# ESP32_ublox_IMU_2020-12-27_17-32-34.net
KiCad netlist of a schematic drawn in Altium Designer
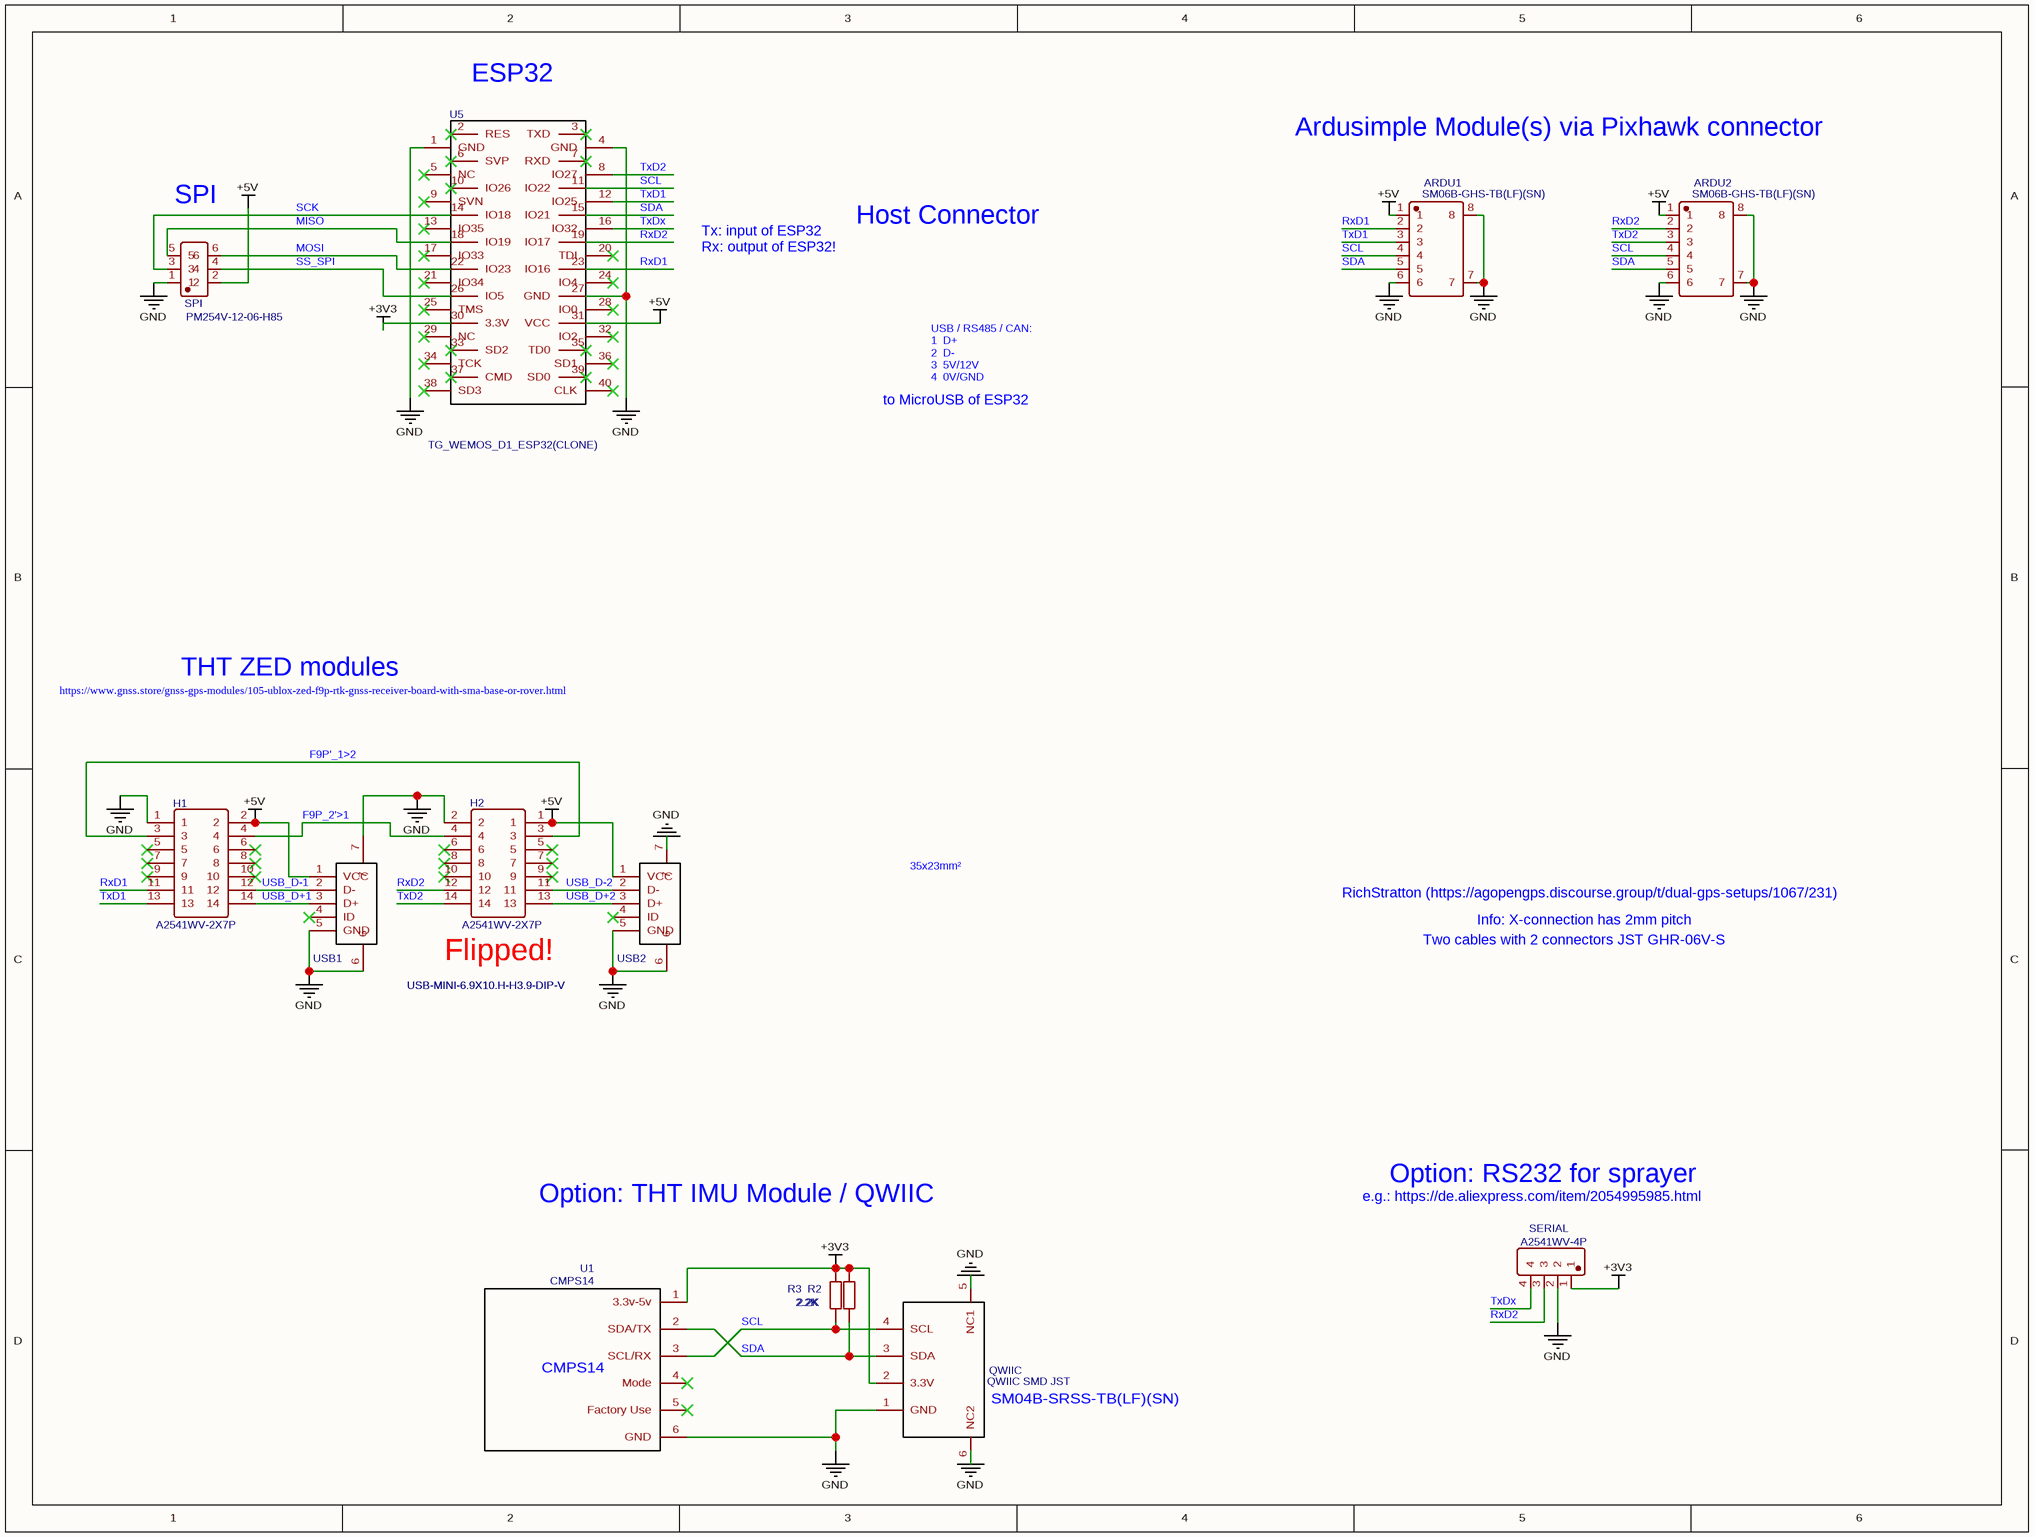
[diagram p0: ESP32 ublox IMU_2020-12-27_17-32-34.schdoc]

(export (version "E")
  (design (tool "Eeschema 10.0.6"))
  (components
    (comp (ref "ARDU1")
      (value "SM06B-GHS-TB(LF)(SN)")
      (fields (field (name "BOM_SUPPLIER PART") "C133065") (field (name "CONTRIBUTOR") "LCSC"))
      (libsource (lib "altium-import") (part "root_0_SM06B-GHS-TB(LF)(SN)_"))
    )
    (comp (ref "ARDU2")
      (value "SM06B-GHS-TB(LF)(SN)")
      (fields (field (name "BOM_SUPPLIER PART") "C133065") (field (name "CONTRIBUTOR") "LCSC"))
      (libsource (lib "altium-import") (part "root_0_SM06B-GHS-TB(LF)(SN)_"))
    )
    (comp (ref "H1")
      (value "A2541WV-2X7P")
      (fields
        (field (name "BOM_SUPPLIER PART") "C225522")
        (field (name "BOM_MANUFACTURER PART") "A2541WV-2x7P")
        (field (name "CONTRIBUTOR") "LCSC")
      )
      (libsource (lib "") (part "root_0_A2541WV-2X7P__1"))
    )
    (comp (ref "H2")
      (value "A2541WV-2X7P")
      (fields
        (field (name "BOM_SUPPLIER PART") "C225522")
        (field (name "BOM_MANUFACTURER PART") "A2541WV-2x7P")
        (field (name "CONTRIBUTOR") "LCSC")
      )
      (libsource (lib "altium-import") (part "root_0_A2541WV-2X7P_"))
    )
    (comp (ref "QWIIC")
      (value "QWIIC SMD JST")
      (fields
        (field (name "BOM_MANUFACTURER PART") "SM04B-SRSS-TB(LF)(SN)")
        (field (name "BOM_SUPPLIER PART") "PRT-14417")
        (field (name "CONTRIBUTOR") "donhagen")
      )
      (libsource (lib "altium-import") (part "root_1_QWIIC SMD JST_"))
    )
    (comp (ref "R2")
      (value "2.2K")
      (fields
        (field (name "BOM_SUPPLIER PART") "C274429")
        (field (name "BOM_MANUFACTURER PART") "RNU18F2201A520NH")
        (field (name "CONTRIBUTOR") "LCSC")
      )
      (libsource (lib "altium-import") (part "root_1_2.2K_"))
    )
    (comp (ref "R3")
      (value "2.2K")
      (fields
        (field (name "BOM_SUPPLIER PART") "C274429")
        (field (name "BOM_MANUFACTURER PART") "RNU18F2201A520NH")
        (field (name "CONTRIBUTOR") "LCSC")
      )
      (libsource (lib "altium-import") (part "root_1_2.2K_"))
    )
    (comp (ref "SERIAL")
      (value "A2541WV-4P")
      (fields (field (name "BOM_SUPPLIER PART") "C225479") (field (name "CONTRIBUTOR") "LCSC"))
      (libsource (lib "altium-import") (part "root_0_A2541WV-4P_"))
    )
    (comp (ref "SPI")
      (value "PM254V-12-06-H85")
      (fields (field (name "BOM_SUPPLIER PART") "C541853") (field (name "CONTRIBUTOR") "LCSC"))
      (libsource (lib "altium-import") (part "root_0_PM254V-12-06-H85_"))
    )
    (comp (ref "U1")
      (value "CMPS14")
      (fields (field (name "CONTRIBUTOR") "FixyNeko"))
      (libsource (lib "altium-import") (part "root_0_CMPS14_"))
    )
    (comp (ref "U5")
      (value "TG_WEMOS_D1_ESP32(CLONE)")
      (fields
        (field (name "BOM_MANUFACTURER PART") "New SchematicLib")
        (field (name "BOM_SUPPLIER PART") "undefined")
        (field (name "CONTRIBUTOR") "John Archbold")
      )
      (libsource (lib "altium-import") (part "root_0_TG_WEMOS_D1_ESP32(CLONE)_"))
    )
    (comp (ref "USB1")
      (value "USB-MINI-6.9X10.H-H3.9-DIP-V")
      (fields (field (name "BOM_SUPPLIER PART") "C13453") (field (name "CONTRIBUTOR") "LCSC"))
      (libsource (lib "altium-import") (part "root_3_USB-MINI-6.9X10.H-H3.9-DIP-V_"))
    )
    (comp (ref "USB2")
      (value "USB-MINI-6.9X10.H-H3.9-DIP-V")
      (fields (field (name "BOM_SUPPLIER PART") "C13453") (field (name "CONTRIBUTOR") "LCSC"))
      (libsource (lib "altium-import") (part "root_3_USB-MINI-6.9X10.H-H3.9-DIP-V_"))
    )
  )
  (nets
    (net (code "1") (name "+3V3") (class "Default")
      (node (ref "QWIIC") (pin "2") (pinfunction "3.3V_2") (pintype "passive"))
      (node (ref "R2") (pin "2") (pinfunction "2_2") (pintype "passive"))
      (node (ref "R3") (pin "2") (pinfunction "2_2") (pintype "passive"))
      (node (ref "SERIAL") (pin "1") (pinfunction "1_1") (pintype "passive"))
      (node (ref "U1") (pin "1") (pinfunction "3.3v-5v_1") (pintype "passive"))
      (node (ref "U5") (pin "30") (pinfunction "3.3V_30") (pintype "passive"))
    )
    (net (code "2") (name "+5V") (class "Default")
      (node (ref "ARDU1") (pin "1") (pinfunction "1_1") (pintype "passive"))
      (node (ref "ARDU2") (pin "1") (pinfunction "1_1") (pintype "passive"))
      (node (ref "H1") (pin "2") (pinfunction "2_2") (pintype "passive"))
      (node (ref "H2") (pin "1") (pinfunction "1_1") (pintype "passive"))
      (node (ref "SPI") (pin "2") (pinfunction "2_2") (pintype "passive"))
      (node (ref "U5") (pin "31") (pinfunction "VCC_31") (pintype "passive"))
      (node (ref "USB1") (pin "1") (pinfunction "VCC_1") (pintype "passive"))
      (node (ref "USB2") (pin "1") (pinfunction "VCC_1") (pintype "passive"))
    )
    (net (code "3") (name "/F9P'_1>2") (class "Default")
      (node (ref "H1") (pin "3") (pinfunction "3_3") (pintype "passive"))
      (node (ref "H2") (pin "3") (pinfunction "3_3") (pintype "passive"))
    )
    (net (code "4") (name "/F9P_2'>1") (class "Default")
      (node (ref "H1") (pin "4") (pinfunction "4_4") (pintype "passive"))
      (node (ref "H2") (pin "4") (pinfunction "4_4") (pintype "passive"))
    )
    (net (code "5") (name "/MISO") (class "Default")
      (node (ref "SPI") (pin "5") (pinfunction "5_5") (pintype "passive"))
      (node (ref "U5") (pin "18") (pinfunction "IO19_18") (pintype "passive"))
    )
    (net (code "6") (name "/MOSI") (class "Default")
      (node (ref "SPI") (pin "6") (pinfunction "6_6") (pintype "passive"))
      (node (ref "U5") (pin "22") (pinfunction "IO23_22") (pintype "passive"))
    )
    (net (code "7") (name "/RxD1") (class "Default")
      (node (ref "ARDU1") (pin "2") (pinfunction "2_2") (pintype "passive"))
      (node (ref "H1") (pin "11") (pinfunction "11_11") (pintype "passive"))
      (node (ref "U5") (pin "23") (pinfunction "IO16_23") (pintype "passive"))
    )
    (net (code "8") (name "/RxD2") (class "Default")
      (node (ref "ARDU2") (pin "2") (pinfunction "2_2") (pintype "passive"))
      (node (ref "H2") (pin "12") (pinfunction "12_12") (pintype "passive"))
      (node (ref "SERIAL") (pin "3") (pinfunction "3_3") (pintype "passive"))
      (node (ref "U5") (pin "19") (pinfunction "IO17_19") (pintype "passive"))
    )
    (net (code "9") (name "/SCK") (class "Default")
      (node (ref "SPI") (pin "3") (pinfunction "3_3") (pintype "passive"))
      (node (ref "U5") (pin "14") (pinfunction "IO18_14") (pintype "passive"))
    )
    (net (code "10") (name "/SCL") (class "Default")
      (node (ref "ARDU1") (pin "4") (pinfunction "4_4") (pintype "passive"))
      (node (ref "ARDU2") (pin "4") (pinfunction "4_4") (pintype "passive"))
      (node (ref "QWIIC") (pin "4") (pinfunction "SCL_4") (pintype "passive"))
      (node (ref "R3") (pin "1") (pinfunction "1_1") (pintype "passive"))
      (node (ref "U1") (pin "3") (pinfunction "SCL/RX_3") (pintype "passive"))
      (node (ref "U5") (pin "11") (pinfunction "IO22_11") (pintype "passive"))
    )
    (net (code "11") (name "/SDA") (class "Default")
      (node (ref "ARDU1") (pin "5") (pinfunction "5_5") (pintype "passive"))
      (node (ref "ARDU2") (pin "5") (pinfunction "5_5") (pintype "passive"))
      (node (ref "QWIIC") (pin "3") (pinfunction "SDA_3") (pintype "passive"))
      (node (ref "R2") (pin "1") (pinfunction "1_1") (pintype "passive"))
      (node (ref "U1") (pin "2") (pinfunction "SDA/TX_2") (pintype "passive"))
      (node (ref "U5") (pin "15") (pinfunction "IO21_15") (pintype "passive"))
    )
    (net (code "12") (name "/SS_SPI") (class "Default")
      (node (ref "SPI") (pin "4") (pinfunction "4_4") (pintype "passive"))
      (node (ref "U5") (pin "26") (pinfunction "IO5_26") (pintype "passive"))
    )
    (net (code "13") (name "/TxD1") (class "Default")
      (node (ref "ARDU1") (pin "3") (pinfunction "3_3") (pintype "passive"))
      (node (ref "H1") (pin "13") (pinfunction "13_13") (pintype "passive"))
      (node (ref "U5") (pin "12") (pinfunction "IO25_12") (pintype "passive"))
    )
    (net (code "14") (name "/TxD2") (class "Default")
      (node (ref "ARDU2") (pin "3") (pinfunction "3_3") (pintype "passive"))
      (node (ref "H2") (pin "14") (pinfunction "14_14") (pintype "passive"))
      (node (ref "U5") (pin "8") (pinfunction "IO27_8") (pintype "passive"))
    )
    (net (code "15") (name "/TxDx") (class "Default")
      (node (ref "SERIAL") (pin "4") (pinfunction "4_4") (pintype "passive"))
      (node (ref "U5") (pin "16") (pinfunction "IO32_16") (pintype "passive"))
    )
    (net (code "16") (name "/USB_D+1") (class "Default")
      (node (ref "H1") (pin "14") (pinfunction "14_14") (pintype "passive"))
      (node (ref "USB1") (pin "3") (pinfunction "D+_3") (pintype "passive"))
    )
    (net (code "17") (name "/USB_D+2") (class "Default")
      (node (ref "H2") (pin "13") (pinfunction "13_13") (pintype "passive"))
      (node (ref "USB2") (pin "3") (pinfunction "D+_3") (pintype "passive"))
    )
    (net (code "18") (name "/USB_D-1") (class "Default")
      (node (ref "H1") (pin "12") (pinfunction "12_12") (pintype "passive"))
      (node (ref "USB1") (pin "2") (pinfunction "D-_2") (pintype "passive"))
    )
    (net (code "19") (name "/USB_D-2") (class "Default")
      (node (ref "H2") (pin "11") (pinfunction "11_11") (pintype "passive"))
      (node (ref "USB2") (pin "2") (pinfunction "D-_2") (pintype "passive"))
    )
    (net (code "20") (name "GND") (class "Default")
      (node (ref "ARDU1") (pin "6") (pinfunction "6_6") (pintype "passive"))
      (node (ref "ARDU1") (pin "7") (pinfunction "7_7") (pintype "passive"))
      (node (ref "ARDU1") (pin "8") (pinfunction "8_8") (pintype "passive"))
      (node (ref "ARDU2") (pin "6") (pinfunction "6_6") (pintype "passive"))
      (node (ref "ARDU2") (pin "7") (pinfunction "7_7") (pintype "passive"))
      (node (ref "ARDU2") (pin "8") (pinfunction "8_8") (pintype "passive"))
      (node (ref "H1") (pin "1") (pinfunction "1_1") (pintype "passive"))
      (node (ref "H2") (pin "2") (pinfunction "2_2") (pintype "passive"))
      (node (ref "QWIIC") (pin "1") (pinfunction "GND_1") (pintype "passive"))
      (node (ref "QWIIC") (pin "5") (pinfunction "NC1_5") (pintype "passive"))
      (node (ref "QWIIC") (pin "6") (pinfunction "NC2_6") (pintype "passive"))
      (node (ref "SERIAL") (pin "2") (pinfunction "2_2") (pintype "passive"))
      (node (ref "SPI") (pin "1") (pinfunction "1_1") (pintype "passive"))
      (node (ref "U1") (pin "6") (pinfunction "GND_6") (pintype "passive"))
      (node (ref "U5") (pin "1") (pinfunction "GND_1") (pintype "passive"))
      (node (ref "U5") (pin "27") (pinfunction "GND_27") (pintype "passive"))
      (node (ref "U5") (pin "4") (pinfunction "GND_4") (pintype "passive"))
      (node (ref "USB1") (pin "5") (pinfunction "GND_5") (pintype "passive"))
      (node (ref "USB1") (pin "6") (pinfunction "6_6") (pintype "passive"))
      (node (ref "USB1") (pin "7") (pinfunction "7_7") (pintype "passive"))
      (node (ref "USB2") (pin "5") (pinfunction "GND_5") (pintype "passive"))
      (node (ref "USB2") (pin "6") (pinfunction "6_6") (pintype "passive"))
      (node (ref "USB2") (pin "7") (pinfunction "7_7") (pintype "passive"))
    )
    (net (code "21") (name "unconnected-(H1-Pad5)") (class "Default")
      (node (ref "H1") (pin "5") (pinfunction "5_5") (pintype "passive+no_connect"))
    )
    (net (code "22") (name "unconnected-(H1-Pad6)") (class "Default")
      (node (ref "H1") (pin "6") (pinfunction "6_6") (pintype "passive+no_connect"))
    )
    (net (code "23") (name "unconnected-(H1-Pad7)") (class "Default")
      (node (ref "H1") (pin "7") (pinfunction "7_7") (pintype "passive+no_connect"))
    )
    (net (code "24") (name "unconnected-(H1-Pad8)") (class "Default")
      (node (ref "H1") (pin "8") (pinfunction "8_8") (pintype "passive+no_connect"))
    )
    (net (code "25") (name "unconnected-(H1-Pad9)") (class "Default")
      (node (ref "H1") (pin "9") (pinfunction "9_9") (pintype "passive+no_connect"))
    )
    (net (code "26") (name "unconnected-(H1-Pad10)") (class "Default")
      (node (ref "H1") (pin "10") (pinfunction "10_10") (pintype "passive+no_connect"))
    )
    (net (code "27") (name "unconnected-(H2-Pad5)") (class "Default")
      (node (ref "H2") (pin "5") (pinfunction "5_5") (pintype "passive+no_connect"))
    )
    (net (code "28") (name "unconnected-(H2-Pad6)") (class "Default")
      (node (ref "H2") (pin "6") (pinfunction "6_6") (pintype "passive+no_connect"))
    )
    (net (code "29") (name "unconnected-(H2-Pad7)") (class "Default")
      (node (ref "H2") (pin "7") (pinfunction "7_7") (pintype "passive+no_connect"))
    )
    (net (code "30") (name "unconnected-(H2-Pad8)") (class "Default")
      (node (ref "H2") (pin "8") (pinfunction "8_8") (pintype "passive+no_connect"))
    )
    (net (code "31") (name "unconnected-(H2-Pad9)") (class "Default")
      (node (ref "H2") (pin "9") (pinfunction "9_9") (pintype "passive+no_connect"))
    )
    (net (code "32") (name "unconnected-(H2-Pad10)") (class "Default")
      (node (ref "H2") (pin "10") (pinfunction "10_10") (pintype "passive+no_connect"))
    )
    (net (code "33") (name "unconnected-(U1-Factory_Use-Pad5)") (class "Default")
      (node (ref "U1") (pin "5") (pinfunction "Factory_Use_5") (pintype "passive+no_connect"))
    )
    (net (code "34") (name "unconnected-(U1-Mode-Pad4)") (class "Default")
      (node (ref "U1") (pin "4") (pinfunction "Mode_4") (pintype "passive+no_connect"))
    )
    (net (code "35") (name "unconnected-(U5-CLK-Pad40)") (class "Default")
      (node (ref "U5") (pin "40") (pinfunction "CLK_40") (pintype "passive+no_connect"))
    )
    (net (code "36") (name "unconnected-(U5-CMD-Pad37)") (class "Default")
      (node (ref "U5") (pin "37") (pinfunction "CMD_37") (pintype "passive+no_connect"))
    )
    (net (code "37") (name "unconnected-(U5-IO0-Pad28)") (class "Default")
      (node (ref "U5") (pin "28") (pinfunction "IO0_28") (pintype "passive+no_connect"))
    )
    (net (code "38") (name "unconnected-(U5-IO2-Pad32)") (class "Default")
      (node (ref "U5") (pin "32") (pinfunction "IO2_32") (pintype "passive+no_connect"))
    )
    (net (code "39") (name "unconnected-(U5-IO4-Pad24)") (class "Default")
      (node (ref "U5") (pin "24") (pinfunction "IO4_24") (pintype "passive+no_connect"))
    )
    (net (code "40") (name "unconnected-(U5-IO26-Pad10)") (class "Default")
      (node (ref "U5") (pin "10") (pinfunction "IO26_10") (pintype "passive+no_connect"))
    )
    (net (code "41") (name "unconnected-(U5-IO33-Pad17)") (class "Default")
      (node (ref "U5") (pin "17") (pinfunction "IO33_17") (pintype "passive+no_connect"))
    )
    (net (code "42") (name "unconnected-(U5-IO34-Pad21)") (class "Default")
      (node (ref "U5") (pin "21") (pinfunction "IO34_21") (pintype "passive+no_connect"))
    )
    (net (code "43") (name "unconnected-(U5-IO35-Pad13)") (class "Default")
      (node (ref "U5") (pin "13") (pinfunction "IO35_13") (pintype "passive+no_connect"))
    )
    (net (code "44") (name "unconnected-(U5-NC-Pad5)") (class "Default")
      (node (ref "U5") (pin "5") (pinfunction "NC_5") (pintype "passive+no_connect"))
    )
    (net (code "45") (name "unconnected-(U5-NC-Pad29)") (class "Default")
      (node (ref "U5") (pin "29") (pinfunction "NC_29") (pintype "passive+no_connect"))
    )
    (net (code "46") (name "unconnected-(U5-RES-Pad2)") (class "Default")
      (node (ref "U5") (pin "2") (pinfunction "RES_2") (pintype "passive+no_connect"))
    )
    (net (code "47") (name "unconnected-(U5-RXD-Pad7)") (class "Default")
      (node (ref "U5") (pin "7") (pinfunction "RXD_7") (pintype "passive+no_connect"))
    )
    (net (code "48") (name "unconnected-(U5-SD0-Pad39)") (class "Default")
      (node (ref "U5") (pin "39") (pinfunction "SD0_39") (pintype "passive+no_connect"))
    )
    (net (code "49") (name "unconnected-(U5-SD1-Pad36)") (class "Default")
      (node (ref "U5") (pin "36") (pinfunction "SD1_36") (pintype "passive+no_connect"))
    )
    (net (code "50") (name "unconnected-(U5-SD2-Pad33)") (class "Default")
      (node (ref "U5") (pin "33") (pinfunction "SD2_33") (pintype "passive+no_connect"))
    )
    (net (code "51") (name "unconnected-(U5-SD3-Pad38)") (class "Default")
      (node (ref "U5") (pin "38") (pinfunction "SD3_38") (pintype "passive+no_connect"))
    )
    (net (code "52") (name "unconnected-(U5-SVN-Pad9)") (class "Default")
      (node (ref "U5") (pin "9") (pinfunction "SVN_9") (pintype "passive+no_connect"))
    )
    (net (code "53") (name "unconnected-(U5-SVP-Pad6)") (class "Default")
      (node (ref "U5") (pin "6") (pinfunction "SVP_6") (pintype "passive+no_connect"))
    )
    (net (code "54") (name "unconnected-(U5-TCK-Pad34)") (class "Default")
      (node (ref "U5") (pin "34") (pinfunction "TCK_34") (pintype "passive+no_connect"))
    )
    (net (code "55") (name "unconnected-(U5-TD0-Pad35)") (class "Default")
      (node (ref "U5") (pin "35") (pinfunction "TD0_35") (pintype "passive+no_connect"))
    )
    (net (code "56") (name "unconnected-(U5-TDI-Pad20)") (class "Default")
      (node (ref "U5") (pin "20") (pinfunction "TDI_20") (pintype "passive+no_connect"))
    )
    (net (code "57") (name "unconnected-(U5-TMS-Pad25)") (class "Default")
      (node (ref "U5") (pin "25") (pinfunction "TMS_25") (pintype "passive+no_connect"))
    )
    (net (code "58") (name "unconnected-(U5-TXD-Pad3)") (class "Default")
      (node (ref "U5") (pin "3") (pinfunction "TXD_3") (pintype "passive+no_connect"))
    )
    (net (code "59") (name "unconnected-(USB1-ID-Pad4)") (class "Default")
      (node (ref "USB1") (pin "4") (pinfunction "ID_4") (pintype "passive+no_connect"))
    )
    (net (code "60") (name "unconnected-(USB2-ID-Pad4)") (class "Default")
      (node (ref "USB2") (pin "4") (pinfunction "ID_4") (pintype "passive+no_connect"))
    )
  )
)
